# slave-basic.net
KiCad netlist of a schematic drawn in EAGLE
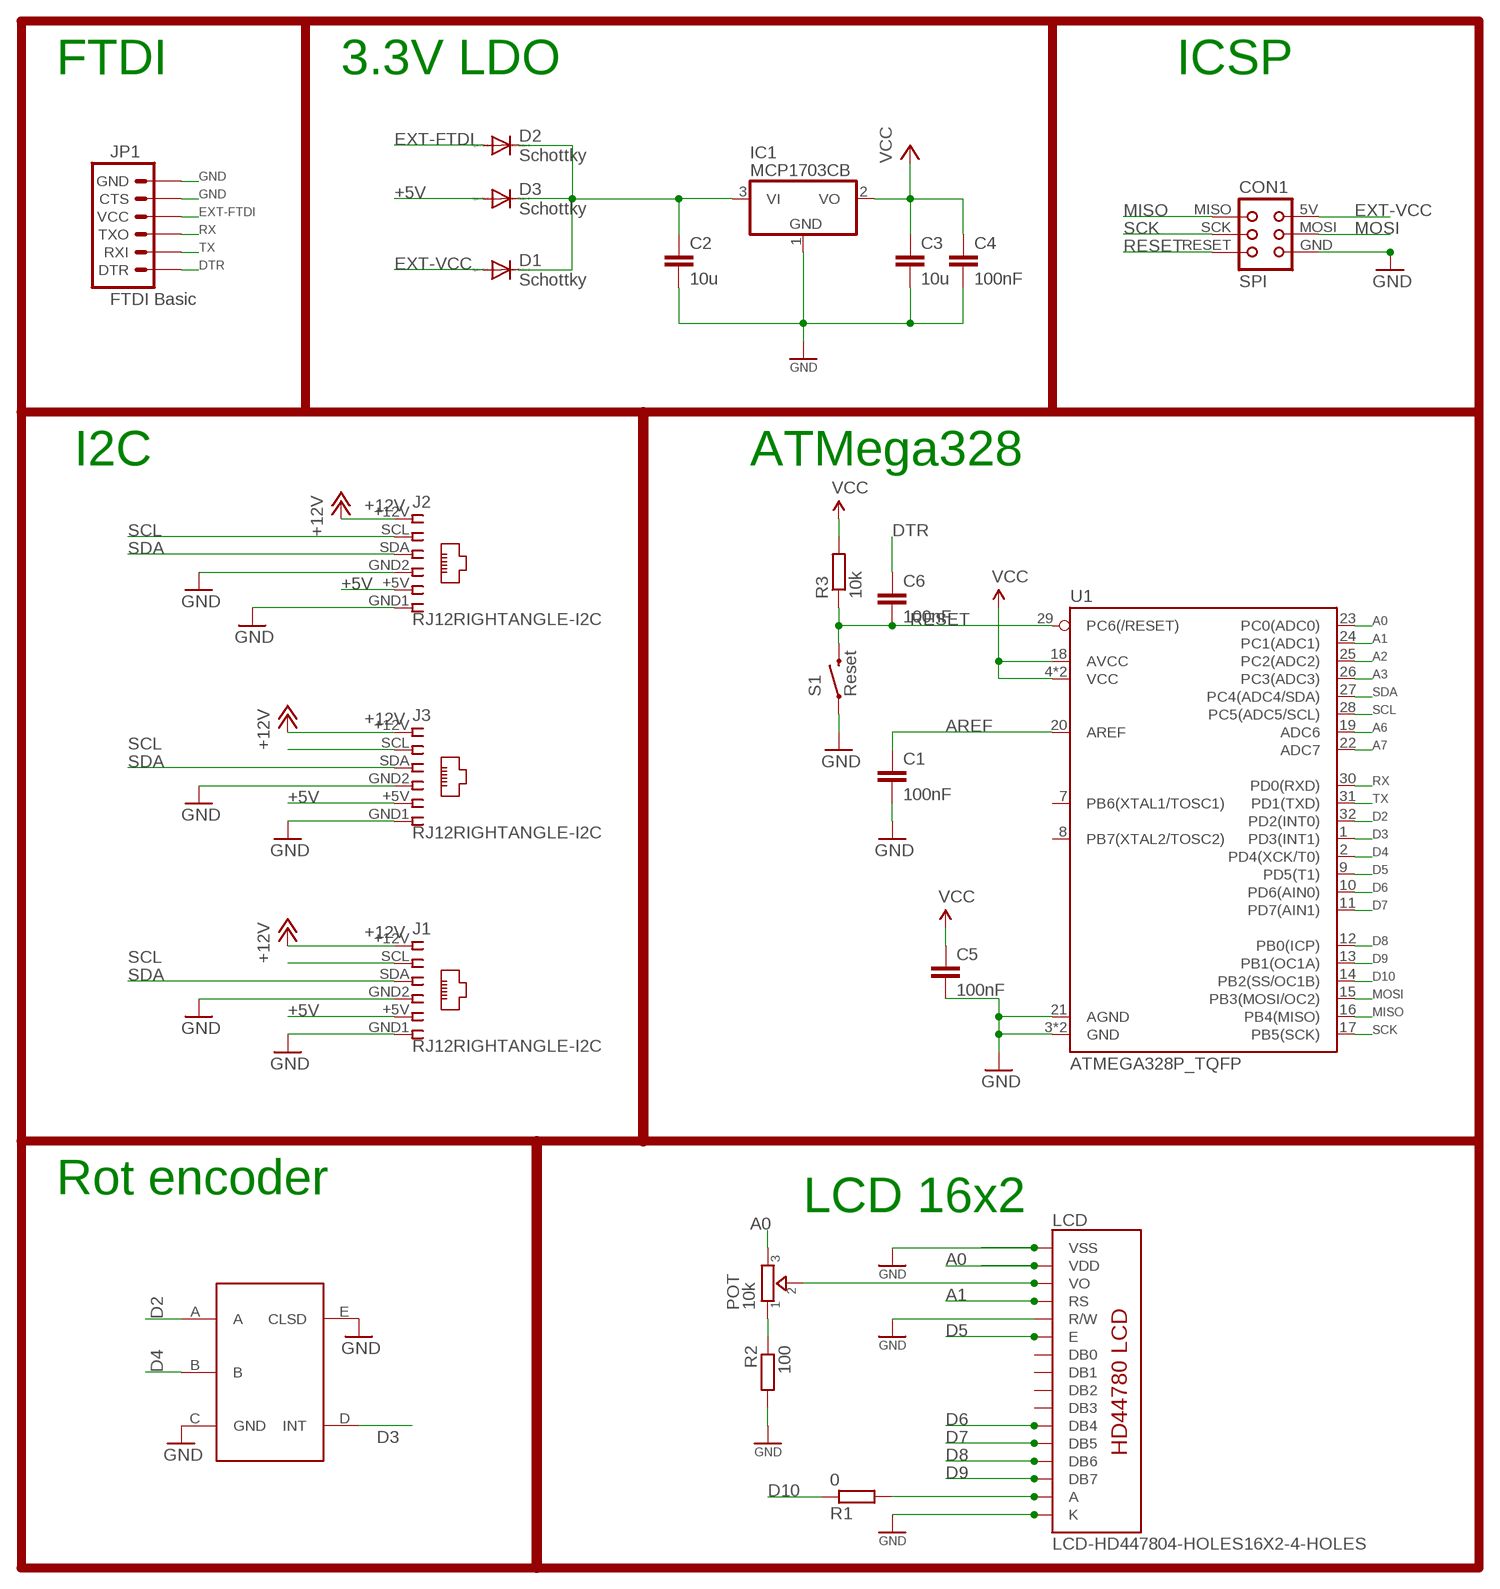
[diagram p0: schematic, sheet 1]

(export (version "E")
  (design (tool "Eeschema 10.0.6"))
  (components
    (comp (ref "C1")
      (value "100nF")
      (footprint "eagle-import:C0805K")
      (fields (field (name "MPN") "80-C1206C104K5R"))
      (libsource (lib "eagle-import") (part "C-EUC0805K"))
    )
    (comp (ref "C2")
      (value "10u")
      (footprint "eagle-import:C0805K")
      (fields (field (name "MPN") "77-VJ1206V106ZXQTBC"))
      (libsource (lib "eagle-import") (part "C-EUC0805K"))
    )
    (comp (ref "C3")
      (value "10u")
      (footprint "eagle-import:C0805K")
      (fields (field (name "MPN") "77-VJ1206V106ZXQTBC"))
      (libsource (lib "eagle-import") (part "C-EUC0805K"))
    )
    (comp (ref "C4")
      (value "100nF")
      (footprint "eagle-import:C0805K")
      (fields (field (name "MPN") "80-C1206C104K5R"))
      (libsource (lib "eagle-import") (part "C-EUC0805K"))
    )
    (comp (ref "C5")
      (value "100nF")
      (footprint "eagle-import:C0805K")
      (fields (field (name "MPN") "80-C1206C104K5R"))
      (libsource (lib "eagle-import") (part "C-EUC0805K"))
    )
    (comp (ref "C6")
      (value "100nF")
      (footprint "eagle-import:C0805K")
      (fields (field (name "MPN") "80-C1206C104K5R"))
      (libsource (lib "eagle-import") (part "C-EUC0805K"))
    )
    (comp (ref "CON1")
      (value "SPI")
      (footprint "eagle-import:TC2030-MCP")
      (libsource (lib "eagle-import") (part "TINYISPTAG"))
    )
    (comp (ref "D1")
      (value "Schottky")
      (footprint "eagle-import:SOD123")
      (fields (field (name "MPN") "621-1N5819HW-F"))
      (libsource (lib "eagle-import") (part "MBR0520LT"))
    )
    (comp (ref "D2")
      (value "Schottky")
      (footprint "eagle-import:SOD123")
      (fields (field (name "MPN") "621-1N5819HW-F"))
      (libsource (lib "eagle-import") (part "MBR0520LT"))
    )
    (comp (ref "D3")
      (value "Schottky")
      (footprint "eagle-import:SOD123")
      (fields (field (name "MPN") "621-1N5819HW-F"))
      (libsource (lib "eagle-import") (part "MBR0520LT"))
    )
    (comp (ref "IC1")
      (value "MCP1703CB")
      (footprint "eagle-import:SOT23")
      (libsource (lib "eagle-import") (part "MCP1703CB"))
    )
    (comp (ref "J1")
      (value "RJ12RIGHTANGLE-I2C")
      (footprint "eagle-import:RJ12-RIGHTANGLE-I2C")
      (libsource (lib "eagle-import") (part "RJ12RIGHTANGLE-I2C"))
    )
    (comp (ref "J2")
      (value "RJ12RIGHTANGLE-I2C")
      (footprint "eagle-import:RJ12-RIGHTANGLE-I2C")
      (libsource (lib "eagle-import") (part "RJ12RIGHTANGLE-I2C"))
    )
    (comp (ref "J3")
      (value "RJ12RIGHTANGLE-I2C")
      (footprint "eagle-import:RJ12-RIGHTANGLE-I2C")
      (libsource (lib "eagle-import") (part "RJ12RIGHTANGLE-I2C"))
    )
    (comp (ref "JP1")
      (value "FTDI Basic")
      (footprint "eagle-import:1X06")
      (libsource (lib "eagle-import") (part "ARDUINO_SERIAL_PROGRAMPTH"))
    )
    (comp (ref "LCD")
      (value "LCD-HD447804-HOLES16X2-4-HOLES")
      (footprint "eagle-import:LCD-16X2-4HOLES")
      (libsource (lib "eagle-import") (part "LCD-HD4478016X2-4-HOLES4-HOLES"))
    )
    (comp (ref "POT")
      (value "10k")
      (footprint "eagle-import:TRIMMER_3362P")
      (libsource (lib "eagle-import") (part "TRIMMER-3362P"))
    )
    (comp (ref "R1")
      (value "0")
      (footprint "eagle-import:R0805")
      (libsource (lib "eagle-import") (part "rcl_334_R-EU_R0805"))
    )
    (comp (ref "R2")
      (value "100")
      (footprint "eagle-import:R0805")
      (libsource (lib "eagle-import") (part "R-EU_R0805"))
    )
    (comp (ref "R3")
      (value "10k")
      (footprint "eagle-import:R0805")
      (libsource (lib "eagle-import") (part "R-EU_R0805"))
    )
    (comp (ref "S1")
      (value "Reset")
      (footprint "eagle-import:TACTILE-SWITCH-SMD-ALT01")
      (libsource (lib "eagle-import") (part "SWITCH-MOMENTARY-2SMD-ALT01"))
    )
    (comp (ref "U$1")
      (value "EC11E")
      (footprint "eagle-import:EC11E")
      (libsource (lib "eagle-import") (part "EC11E"))
    )
    (comp (ref "U1")
      (value "ATMEGA328P_TQFP")
      (footprint "eagle-import:TQFP32-08")
      (libsource (lib "eagle-import") (part "ATMEGA328P_TQFP"))
    )
  )
  (nets
    (net (code "1") (name "+12V") (class "Default")
      (node (ref "J1") (pin "+12V") (pinfunction "1_+12V") (pintype "bidirectional"))
      (node (ref "J2") (pin "+12V") (pinfunction "1_+12V") (pintype "bidirectional"))
      (node (ref "J3") (pin "+12V") (pinfunction "1_+12V") (pintype "bidirectional"))
    )
    (net (code "2") (name "/+5V") (class "Default")
      (node (ref "D3") (pin "A") (pinfunction "A_A") (pintype "passive"))
      (node (ref "J1") (pin "+5V") (pinfunction "5_+5V") (pintype "bidirectional"))
      (node (ref "J2") (pin "+5V") (pinfunction "5_+5V") (pintype "bidirectional"))
      (node (ref "J3") (pin "+5V") (pinfunction "5_+5V") (pintype "bidirectional"))
    )
    (net (code "3") (name "/A0") (class "Default")
      (node (ref "LCD") (pin "2") (pinfunction "VDD_2") (pintype "power_in"))
      (node (ref "POT") (pin "3") (pinfunction "3_3") (pintype "passive"))
      (node (ref "U1") (pin "23") (pinfunction "PC0(ADC0)_23") (pintype "bidirectional"))
    )
    (net (code "4") (name "/A1") (class "Default")
      (node (ref "LCD") (pin "4") (pinfunction "RS_4") (pintype "input"))
      (node (ref "U1") (pin "24") (pinfunction "PC1(ADC1)_24") (pintype "bidirectional"))
    )
    (net (code "5") (name "/A2") (class "Default")
      (node (ref "U1") (pin "25") (pinfunction "PC2(ADC2)_25") (pintype "bidirectional"))
    )
    (net (code "6") (name "/A3") (class "Default")
      (node (ref "U1") (pin "26") (pinfunction "PC3(ADC3)_26") (pintype "bidirectional"))
    )
    (net (code "7") (name "/A6") (class "Default")
      (node (ref "U1") (pin "19") (pinfunction "ADC6_19") (pintype "bidirectional"))
    )
    (net (code "8") (name "/A7") (class "Default")
      (node (ref "U1") (pin "22") (pinfunction "ADC7_22") (pintype "bidirectional"))
    )
    (net (code "9") (name "/AREF") (class "Default")
      (node (ref "C1") (pin "1") (pinfunction "1_1") (pintype "passive"))
      (node (ref "U1") (pin "20") (pinfunction "AREF_20") (pintype "bidirectional"))
    )
    (net (code "10") (name "/D2") (class "Default")
      (node (ref "U$1") (pin "A") (pinfunction "A_A") (pintype "bidirectional"))
      (node (ref "U1") (pin "32") (pinfunction "PD2(INT0)_32") (pintype "bidirectional"))
    )
    (net (code "11") (name "/D3") (class "Default")
      (node (ref "U$1") (pin "D") (pinfunction "INT_D") (pintype "bidirectional"))
      (node (ref "U1") (pin "1") (pinfunction "PD3(INT1)_1") (pintype "bidirectional"))
    )
    (net (code "12") (name "/D4") (class "Default")
      (node (ref "U$1") (pin "B") (pinfunction "B_B") (pintype "bidirectional"))
      (node (ref "U1") (pin "2") (pinfunction "PD4(XCK/T0)_2") (pintype "bidirectional"))
    )
    (net (code "13") (name "/D5") (class "Default")
      (node (ref "LCD") (pin "6") (pinfunction "E_6") (pintype "input"))
      (node (ref "U1") (pin "9") (pinfunction "PD5(T1)_9") (pintype "bidirectional"))
    )
    (net (code "14") (name "/D6") (class "Default")
      (node (ref "LCD") (pin "11") (pinfunction "DB4_11") (pintype "bidirectional"))
      (node (ref "U1") (pin "10") (pinfunction "PD6(AIN0)_10") (pintype "bidirectional"))
    )
    (net (code "15") (name "/D7") (class "Default")
      (node (ref "LCD") (pin "12") (pinfunction "DB5_12") (pintype "bidirectional"))
      (node (ref "U1") (pin "11") (pinfunction "PD7(AIN1)_11") (pintype "bidirectional"))
    )
    (net (code "16") (name "/D8") (class "Default")
      (node (ref "LCD") (pin "13") (pinfunction "DB6_13") (pintype "bidirectional"))
      (node (ref "U1") (pin "12") (pinfunction "PB0(ICP)_12") (pintype "bidirectional"))
    )
    (net (code "17") (name "/D9") (class "Default")
      (node (ref "LCD") (pin "14") (pinfunction "DB7_14") (pintype "bidirectional"))
      (node (ref "U1") (pin "13") (pinfunction "PB1(OC1A)_13") (pintype "bidirectional"))
    )
    (net (code "18") (name "/D10") (class "Default")
      (node (ref "R1") (pin "1") (pinfunction "1_1") (pintype "passive"))
      (node (ref "U1") (pin "14") (pinfunction "PB2(SS/OC1B)_14") (pintype "bidirectional"))
    )
    (net (code "19") (name "/DTR") (class "Default")
      (node (ref "C6") (pin "1") (pinfunction "1_1") (pintype "passive"))
      (node (ref "JP1") (pin "1") (pinfunction "DTR_1") (pintype "passive"))
    )
    (net (code "20") (name "/EXT-FTDI") (class "Default")
      (node (ref "D2") (pin "A") (pinfunction "A_A") (pintype "passive"))
      (node (ref "JP1") (pin "4") (pinfunction "VCC_4") (pintype "passive"))
    )
    (net (code "21") (name "/EXT-VCC") (class "Default")
      (node (ref "CON1") (pin "5V") (pinfunction "VCC_5V") (pintype "passive"))
      (node (ref "D1") (pin "A") (pinfunction "A_A") (pintype "passive"))
    )
    (net (code "22") (name "/MISO") (class "Default")
      (node (ref "CON1") (pin "MISO") (pinfunction "MISO_MISO") (pintype "passive"))
      (node (ref "U1") (pin "16") (pinfunction "PB4(MISO)_16") (pintype "bidirectional"))
    )
    (net (code "23") (name "/MOSI") (class "Default")
      (node (ref "CON1") (pin "MOSI") (pinfunction "MOSI_MOSI") (pintype "passive"))
      (node (ref "U1") (pin "15") (pinfunction "PB3(MOSI/OC2)_15") (pintype "bidirectional"))
    )
    (net (code "24") (name "/RESET") (class "Default")
      (node (ref "C6") (pin "2") (pinfunction "2_2") (pintype "passive"))
      (node (ref "CON1") (pin "RESET") (pinfunction "RESET_RESET") (pintype "passive"))
      (node (ref "R3") (pin "1") (pinfunction "1_1") (pintype "passive"))
      (node (ref "S1") (pin "3") (pinfunction "2_3") (pintype "passive"))
      (node (ref "S1") (pin "4") (pinfunction "2_4") (pintype "passive"))
      (node (ref "U1") (pin "29") (pinfunction "PC6(/RESET)_29") (pintype "bidirectional"))
    )
    (net (code "25") (name "/RX") (class "Default")
      (node (ref "JP1") (pin "3") (pinfunction "TXO_3") (pintype "passive"))
      (node (ref "U1") (pin "30") (pinfunction "PD0(RXD)_30") (pintype "bidirectional"))
    )
    (net (code "26") (name "/SCK") (class "Default")
      (node (ref "CON1") (pin "SCK") (pinfunction "SCK_SCK") (pintype "passive"))
      (node (ref "U1") (pin "17") (pinfunction "PB5(SCK)_17") (pintype "bidirectional"))
    )
    (net (code "27") (name "/SCL") (class "Default")
      (node (ref "J1") (pin "SCL") (pinfunction "2_SCL") (pintype "bidirectional"))
      (node (ref "J2") (pin "SCL") (pinfunction "2_SCL") (pintype "bidirectional"))
      (node (ref "J3") (pin "SCL") (pinfunction "2_SCL") (pintype "bidirectional"))
      (node (ref "U1") (pin "28") (pinfunction "PC5(ADC5/SCL)_28") (pintype "bidirectional"))
    )
    (net (code "28") (name "/SDA") (class "Default")
      (node (ref "J1") (pin "SDA") (pinfunction "3_SDA") (pintype "bidirectional"))
      (node (ref "J2") (pin "SDA") (pinfunction "3_SDA") (pintype "bidirectional"))
      (node (ref "J3") (pin "SDA") (pinfunction "3_SDA") (pintype "bidirectional"))
      (node (ref "U1") (pin "27") (pinfunction "PC4(ADC4/SDA)_27") (pintype "bidirectional"))
    )
    (net (code "29") (name "/TX") (class "Default")
      (node (ref "JP1") (pin "2") (pinfunction "RXI_2") (pintype "passive"))
      (node (ref "U1") (pin "31") (pinfunction "PD1(TXD)_31") (pintype "bidirectional"))
    )
    (net (code "30") (name "GND") (class "Default")
      (node (ref "C1") (pin "2") (pinfunction "2_2") (pintype "passive"))
      (node (ref "C2") (pin "2") (pinfunction "2_2") (pintype "passive"))
      (node (ref "C3") (pin "2") (pinfunction "2_2") (pintype "passive"))
      (node (ref "C4") (pin "2") (pinfunction "2_2") (pintype "passive"))
      (node (ref "C5") (pin "2") (pinfunction "2_2") (pintype "passive"))
      (node (ref "CON1") (pin "GND") (pinfunction "GND_GND") (pintype "passive"))
      (node (ref "IC1") (pin "1") (pinfunction "GND_1") (pintype "passive"))
      (node (ref "J1") (pin "GND1") (pinfunction "6_GND1") (pintype "bidirectional"))
      (node (ref "J1") (pin "GND2") (pinfunction "4_GND2") (pintype "bidirectional"))
      (node (ref "J2") (pin "GND1") (pinfunction "6_GND1") (pintype "bidirectional"))
      (node (ref "J2") (pin "GND2") (pinfunction "4_GND2") (pintype "bidirectional"))
      (node (ref "J3") (pin "GND1") (pinfunction "6_GND1") (pintype "bidirectional"))
      (node (ref "J3") (pin "GND2") (pinfunction "4_GND2") (pintype "bidirectional"))
      (node (ref "JP1") (pin "5") (pinfunction "CTS_5") (pintype "passive"))
      (node (ref "JP1") (pin "6") (pinfunction "GND_6") (pintype "passive"))
      (node (ref "LCD") (pin "1") (pinfunction "VSS_1") (pintype "power_in"))
      (node (ref "LCD") (pin "16") (pinfunction "K_16") (pintype "power_in"))
      (node (ref "LCD") (pin "5") (pinfunction "R/W_5") (pintype "input"))
      (node (ref "R2") (pin "2") (pinfunction "2_2") (pintype "passive"))
      (node (ref "S1") (pin "1") (pinfunction "1_1") (pintype "passive"))
      (node (ref "S1") (pin "2") (pinfunction "1_2") (pintype "passive"))
      (node (ref "U$1") (pin "C") (pinfunction "GND_C") (pintype "bidirectional"))
      (node (ref "U$1") (pin "E") (pinfunction "CLSD_E") (pintype "bidirectional"))
      (node (ref "U1") (pin "21") (pinfunction "AGND_21") (pintype "bidirectional"))
      (node (ref "U1") (pin "3") (pinfunction "GND_3") (pintype "bidirectional"))
      (node (ref "U1") (pin "5") (pinfunction "GND_5") (pintype "bidirectional"))
    )
    (net (code "31") (name "Net-(IC1-VI)") (class "Default")
      (node (ref "C2") (pin "1") (pinfunction "1_1") (pintype "passive"))
      (node (ref "D1") (pin "C") (pinfunction "C_C") (pintype "passive"))
      (node (ref "D2") (pin "C") (pinfunction "C_C") (pintype "passive"))
      (node (ref "D3") (pin "C") (pinfunction "C_C") (pintype "passive"))
      (node (ref "IC1") (pin "3") (pinfunction "VI_3") (pintype "input"))
    )
    (net (code "32") (name "Net-(LCD-A)") (class "Default")
      (node (ref "LCD") (pin "15") (pinfunction "A_15") (pintype "power_in"))
      (node (ref "R1") (pin "2") (pinfunction "2_2") (pintype "passive"))
    )
    (net (code "33") (name "Net-(LCD-VO)") (class "Default")
      (node (ref "LCD") (pin "3") (pinfunction "VO_3") (pintype "bidirectional"))
      (node (ref "POT") (pin "2") (pinfunction "2_2") (pintype "passive"))
    )
    (net (code "34") (name "Net-(POT-Pad1)") (class "Default")
      (node (ref "POT") (pin "1") (pinfunction "1_1") (pintype "passive"))
      (node (ref "R2") (pin "1") (pinfunction "1_1") (pintype "passive"))
    )
    (net (code "35") (name "VCC") (class "Default")
      (node (ref "C3") (pin "1") (pinfunction "1_1") (pintype "passive"))
      (node (ref "C4") (pin "1") (pinfunction "1_1") (pintype "passive"))
      (node (ref "C5") (pin "1") (pinfunction "1_1") (pintype "passive"))
      (node (ref "IC1") (pin "2") (pinfunction "VO_2") (pintype "passive"))
      (node (ref "R3") (pin "2") (pinfunction "2_2") (pintype "passive"))
      (node (ref "U1") (pin "18") (pinfunction "AVCC_18") (pintype "bidirectional"))
      (node (ref "U1") (pin "4") (pinfunction "VCC_4") (pintype "bidirectional"))
      (node (ref "U1") (pin "6") (pinfunction "VCC_6") (pintype "bidirectional"))
    )
    (net (code "36") (name "unconnected-(LCD-DB0-Pad7)") (class "Default")
      (node (ref "LCD") (pin "7") (pinfunction "DB0_7") (pintype "bidirectional"))
    )
    (net (code "37") (name "unconnected-(LCD-DB1-Pad8)") (class "Default")
      (node (ref "LCD") (pin "8") (pinfunction "DB1_8") (pintype "bidirectional"))
    )
    (net (code "38") (name "unconnected-(LCD-DB2-Pad9)") (class "Default")
      (node (ref "LCD") (pin "9") (pinfunction "DB2_9") (pintype "bidirectional"))
    )
    (net (code "39") (name "unconnected-(LCD-DB3-Pad10)") (class "Default")
      (node (ref "LCD") (pin "10") (pinfunction "DB3_10") (pintype "bidirectional"))
    )
    (net (code "40") (name "unconnected-(U1-PB6(XTAL1{slash}TOSC1)-Pad7)") (class "Default")
      (node (ref "U1") (pin "7") (pinfunction "PB6(XTAL1/TOSC1)_7") (pintype "bidirectional"))
    )
    (net (code "41") (name "unconnected-(U1-PB7(XTAL2{slash}TOSC2)-Pad8)") (class "Default")
      (node (ref "U1") (pin "8") (pinfunction "PB7(XTAL2/TOSC2)_8") (pintype "bidirectional"))
    )
  )
)
